# PowerPCB2.net
KiCad netlist of a schematic drawn in Altium Designer
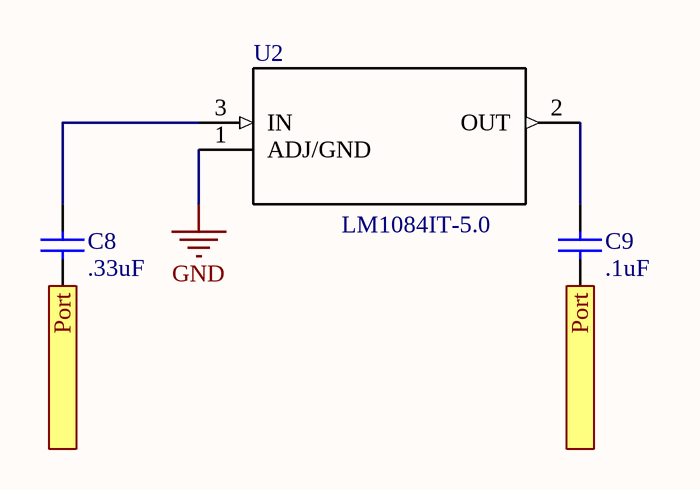
[diagram p0: PowerPCB2.SchDoc]

(export (version "E")
  (design (tool "Eeschema 10.0.6"))
  (components
    (comp (ref "C8")
      (value ".33uF")
      (footprint "CAPC2013X100X45ML10T25")
      (fields (field (name "PART NUMBER") "GRM21AR72A334KAC5L") (field (name "MANUFACTURER") "Murata"))
      (libsource (lib "Altium Content Vault") (part "CAP"))
    )
    (comp (ref "C9")
      (value ".1uF")
      (footprint "CAPC2013X135X45ML10T25")
      (description "Chip Capacitor, 0.1 uF, +/- 10%, 50 V, -55 to 125 degC, 0805 (2012 Metric), RoHS, Tape and Reel")
      (fields (field (name "VOLTAGE") "50V") (field (name "TOLERANCE") "10%"))
      (libsource (lib "Altium Content Vault") (part "CAP-NP-2"))
    )
    (comp (ref "U2")
      (value "LM1084IT-5.0")
      (footprint "*TO254P470X1016X2222-3P")
      (description "Voltage stabiliser; LDO, fixed; 5V; 5A; TO220; THT; 1.2")
      (fields (field (name "MF") "Texas Instruments") (field (name "MP") "LM1084IT-5.0/NOPB"))
      (libsource (lib "LM1084IT-5.0") (part "LM1084IT-5.0"))
    )
  )
  (nets
    (net (code "1") (name "/Port") (class "Default")
      (node (ref "C8") (pin "1") (pinfunction "1_1") (pintype "passive"))
      (node (ref "C9") (pin "1") (pinfunction "1_1") (pintype "passive"))
    )
    (net (code "2") (name "GND") (class "Default")
      (node (ref "U2") (pin "1") (pinfunction "ADJ/GND_1") (pintype "passive"))
    )
    (net (code "3") (name "Net-(U2-IN)") (class "Default")
      (node (ref "C8") (pin "2") (pinfunction "2_2") (pintype "passive"))
      (node (ref "U2") (pin "3") (pinfunction "IN_3") (pintype "input"))
    )
    (net (code "4") (name "Net-(U2-OUT)") (class "Default")
      (node (ref "C9") (pin "2") (pinfunction "2_2") (pintype "passive"))
      (node (ref "U2") (pin "2") (pinfunction "OUT_2") (pintype "output"))
    )
  )
)
